# Protoboard_MX4-7-6.net
KiCad netlist of a schematic drawn in EAGLE
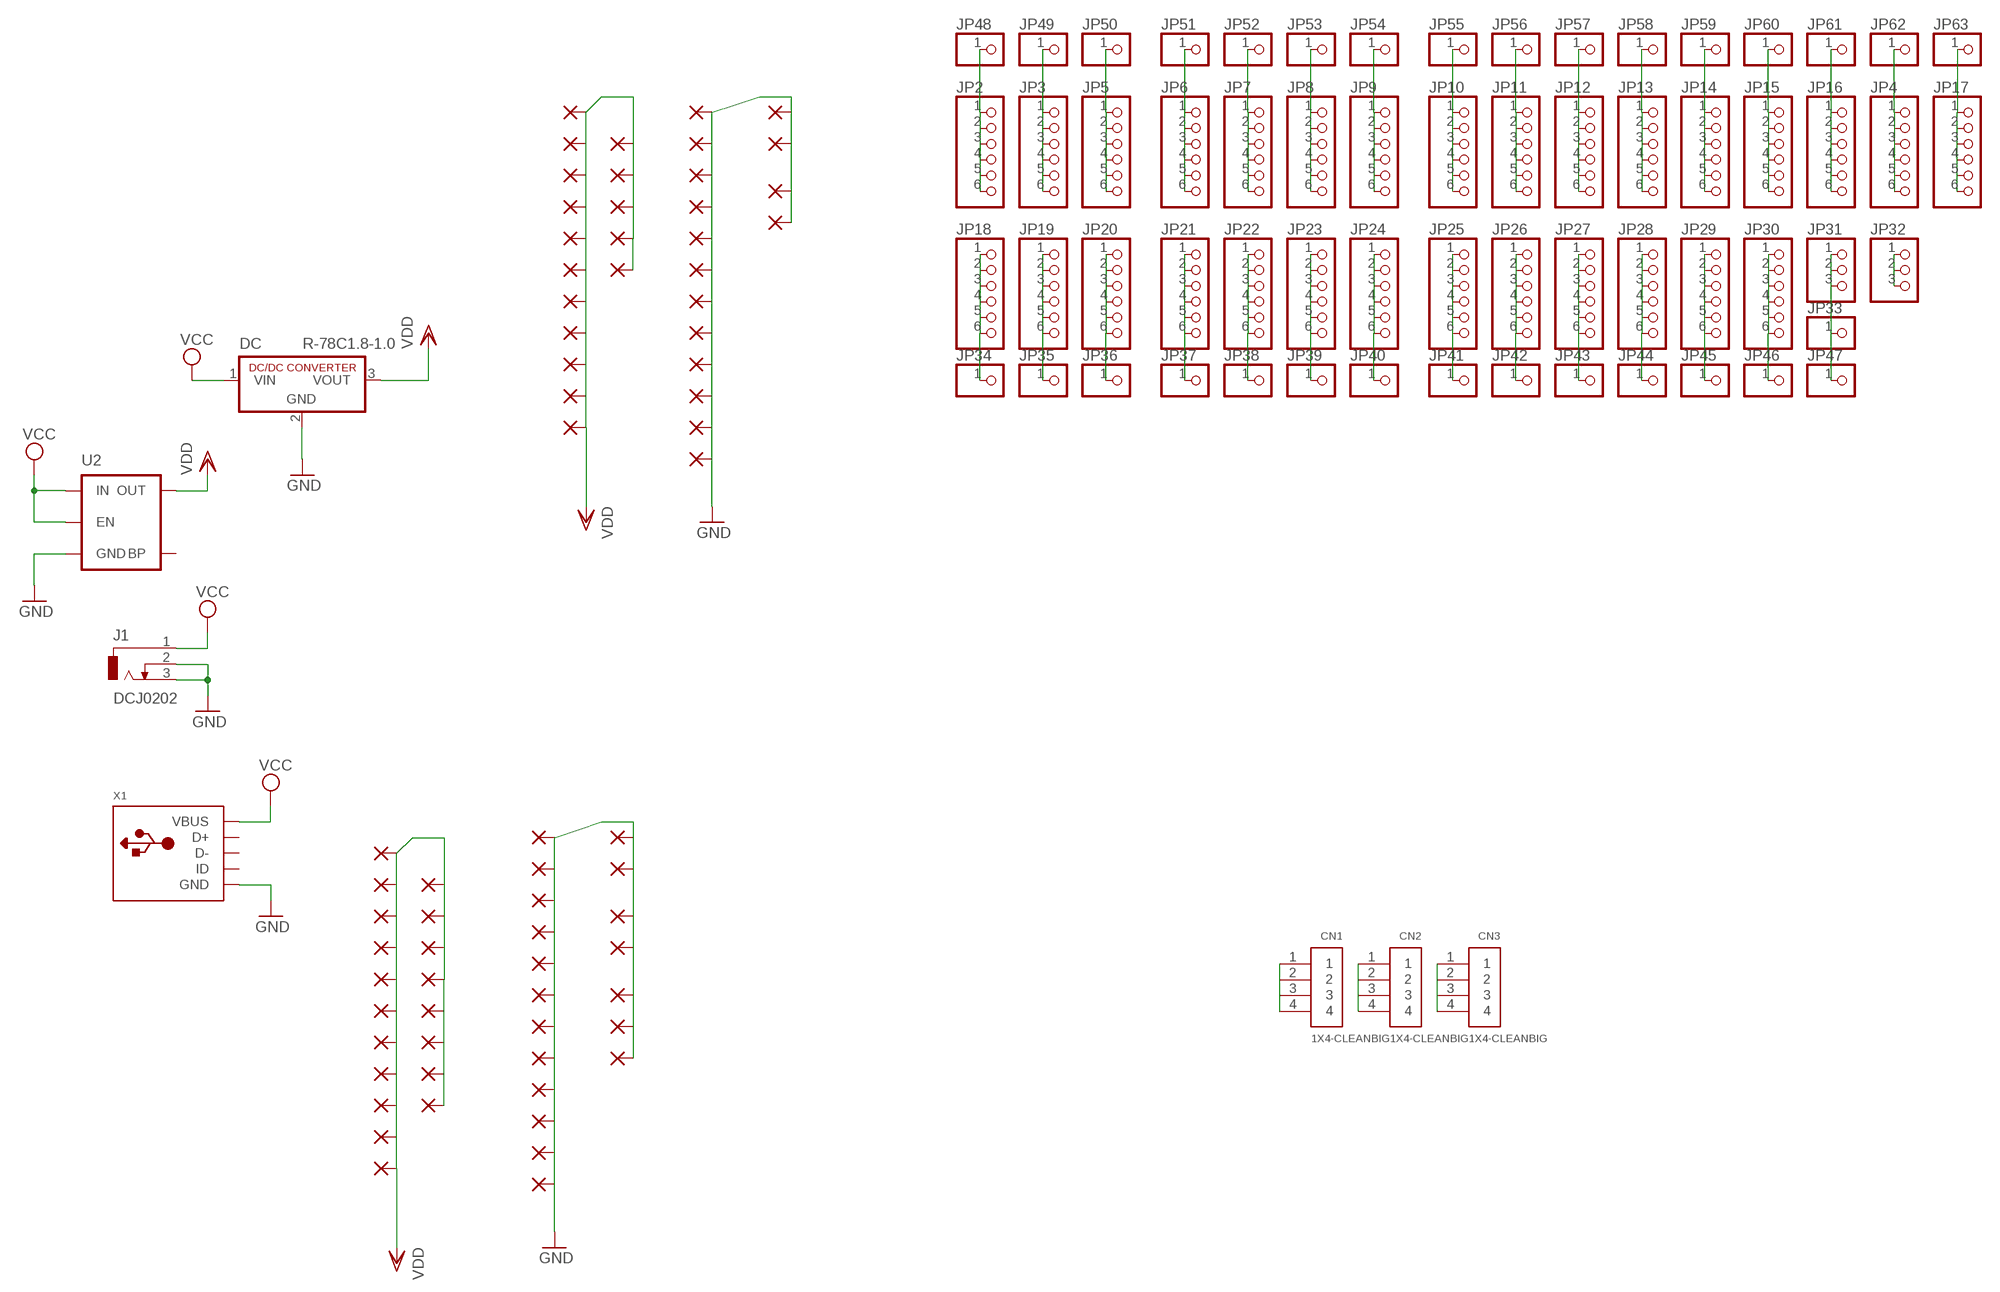
[diagram p0: schematic, sheet 1]

(export (version "E")
  (design (tool "Eeschema 10.0.6"))
  (components
    (comp (ref "CN1")
      (value "1X4-CLEANBIG")
      (footprint "eagle-import:1X04-CLEANBIG")
      (libsource (lib "eagle-import") (part "1X4-CLEANBIG"))
    )
    (comp (ref "CN2")
      (value "1X4-CLEANBIG")
      (footprint "eagle-import:1X04-CLEANBIG")
      (libsource (lib "eagle-import") (part "1X4-CLEANBIG"))
    )
    (comp (ref "CN3")
      (value "1X4-CLEANBIG")
      (footprint "eagle-import:1X04-CLEANBIG")
      (libsource (lib "eagle-import") (part "1X4-CLEANBIG"))
    )
    (comp (ref "DC")
      (value "R-78C1.8-1.0")
      (footprint "eagle-import:SIP3")
      (libsource (lib "eagle-import") (part "R-78C-1.01.8"))
    )
    (comp (ref "J1")
      (value "DCJ0202")
      (footprint "eagle-import:DCJ0202")
      (libsource (lib "eagle-import") (part "DCJ0202"))
    )
    (comp (ref "JP2")
      (value "PINHD-1X6CB")
      (footprint "eagle-import:1X06-CLEANBIG")
      (libsource (lib "eagle-import") (part "PINHD-1X6CB"))
    )
    (comp (ref "JP3")
      (value "PINHD-1X6CB")
      (footprint "eagle-import:1X06-CLEANBIG")
      (libsource (lib "eagle-import") (part "PINHD-1X6CB"))
    )
    (comp (ref "JP4")
      (value "PINHD-1X6CB")
      (footprint "eagle-import:1X06-CLEANBIG")
      (libsource (lib "eagle-import") (part "PINHD-1X6CB"))
    )
    (comp (ref "JP5")
      (value "PINHD-1X6CB")
      (footprint "eagle-import:1X06-CLEANBIG")
      (libsource (lib "eagle-import") (part "PINHD-1X6CB"))
    )
    (comp (ref "JP6")
      (value "PINHD-1X6CB")
      (footprint "eagle-import:1X06-CLEANBIG")
      (libsource (lib "eagle-import") (part "PINHD-1X6CB"))
    )
    (comp (ref "JP7")
      (value "PINHD-1X6CB")
      (footprint "eagle-import:1X06-CLEANBIG")
      (libsource (lib "eagle-import") (part "PINHD-1X6CB"))
    )
    (comp (ref "JP8")
      (value "PINHD-1X6CB")
      (footprint "eagle-import:1X06-CLEANBIG")
      (libsource (lib "eagle-import") (part "PINHD-1X6CB"))
    )
    (comp (ref "JP9")
      (value "PINHD-1X6CB")
      (footprint "eagle-import:1X06-CLEANBIG")
      (libsource (lib "eagle-import") (part "PINHD-1X6CB"))
    )
    (comp (ref "JP10")
      (value "PINHD-1X6CB")
      (footprint "eagle-import:1X06-CLEANBIG")
      (libsource (lib "eagle-import") (part "PINHD-1X6CB"))
    )
    (comp (ref "JP11")
      (value "PINHD-1X6CB")
      (footprint "eagle-import:1X06-CLEANBIG")
      (libsource (lib "eagle-import") (part "PINHD-1X6CB"))
    )
    (comp (ref "JP12")
      (value "PINHD-1X6CB")
      (footprint "eagle-import:1X06-CLEANBIG")
      (libsource (lib "eagle-import") (part "PINHD-1X6CB"))
    )
    (comp (ref "JP13")
      (value "PINHD-1X6CB")
      (footprint "eagle-import:1X06-CLEANBIG")
      (libsource (lib "eagle-import") (part "PINHD-1X6CB"))
    )
    (comp (ref "JP14")
      (value "PINHD-1X6CB")
      (footprint "eagle-import:1X06-CLEANBIG")
      (libsource (lib "eagle-import") (part "PINHD-1X6CB"))
    )
    (comp (ref "JP15")
      (value "PINHD-1X6CB")
      (footprint "eagle-import:1X06-CLEANBIG")
      (libsource (lib "eagle-import") (part "PINHD-1X6CB"))
    )
    (comp (ref "JP16")
      (value "PINHD-1X6CB")
      (footprint "eagle-import:1X06-CLEANBIG")
      (libsource (lib "eagle-import") (part "PINHD-1X6CB"))
    )
    (comp (ref "JP17")
      (value "PINHD-1X6CB")
      (footprint "eagle-import:1X06-CLEANBIG")
      (libsource (lib "eagle-import") (part "PINHD-1X6CB"))
    )
    (comp (ref "JP18")
      (value "PINHD-1X6CB")
      (footprint "eagle-import:1X06-CLEANBIG")
      (libsource (lib "eagle-import") (part "PINHD-1X6CB"))
    )
    (comp (ref "JP19")
      (value "PINHD-1X6CB")
      (footprint "eagle-import:1X06-CLEANBIG")
      (libsource (lib "eagle-import") (part "PINHD-1X6CB"))
    )
    (comp (ref "JP20")
      (value "PINHD-1X6CB")
      (footprint "eagle-import:1X06-CLEANBIG")
      (libsource (lib "eagle-import") (part "PINHD-1X6CB"))
    )
    (comp (ref "JP21")
      (value "PINHD-1X6CB")
      (footprint "eagle-import:1X06-CLEANBIG")
      (libsource (lib "eagle-import") (part "PINHD-1X6CB"))
    )
    (comp (ref "JP22")
      (value "PINHD-1X6CB")
      (footprint "eagle-import:1X06-CLEANBIG")
      (libsource (lib "eagle-import") (part "PINHD-1X6CB"))
    )
    (comp (ref "JP23")
      (value "PINHD-1X6CB")
      (footprint "eagle-import:1X06-CLEANBIG")
      (libsource (lib "eagle-import") (part "PINHD-1X6CB"))
    )
    (comp (ref "JP24")
      (value "PINHD-1X6CB")
      (footprint "eagle-import:1X06-CLEANBIG")
      (libsource (lib "eagle-import") (part "PINHD-1X6CB"))
    )
    (comp (ref "JP25")
      (value "PINHD-1X6CB")
      (footprint "eagle-import:1X06-CLEANBIG")
      (libsource (lib "eagle-import") (part "PINHD-1X6CB"))
    )
    (comp (ref "JP26")
      (value "PINHD-1X6CB")
      (footprint "eagle-import:1X06-CLEANBIG")
      (libsource (lib "eagle-import") (part "PINHD-1X6CB"))
    )
    (comp (ref "JP27")
      (value "PINHD-1X6CB")
      (footprint "eagle-import:1X06-CLEANBIG")
      (libsource (lib "eagle-import") (part "PINHD-1X6CB"))
    )
    (comp (ref "JP28")
      (value "PINHD-1X6CB")
      (footprint "eagle-import:1X06-CLEANBIG")
      (libsource (lib "eagle-import") (part "PINHD-1X6CB"))
    )
    (comp (ref "JP29")
      (value "PINHD-1X6CB")
      (footprint "eagle-import:1X06-CLEANBIG")
      (libsource (lib "eagle-import") (part "PINHD-1X6CB"))
    )
    (comp (ref "JP30")
      (value "PINHD-1X6CB")
      (footprint "eagle-import:1X06-CLEANBIG")
      (libsource (lib "eagle-import") (part "PINHD-1X6CB"))
    )
    (comp (ref "JP31")
      (value "PINHD-1X3CB")
      (footprint "eagle-import:1X03-CLEANBIG")
      (libsource (lib "eagle-import") (part "PINHD-1X3CB"))
    )
    (comp (ref "JP32")
      (value "PINHD-1X3CB")
      (footprint "eagle-import:1X03-CLEANBIG")
      (libsource (lib "eagle-import") (part "PINHD-1X3CB"))
    )
    (comp (ref "JP33")
      (value "PINHD-1X1CB")
      (footprint "eagle-import:1X01-CLEANBIG")
      (libsource (lib "eagle-import") (part "PINHD-1X1CB"))
    )
    (comp (ref "JP34")
      (value "PINHD-1X1CB")
      (footprint "eagle-import:1X01-CLEANBIG")
      (libsource (lib "eagle-import") (part "PINHD-1X1CB"))
    )
    (comp (ref "JP35")
      (value "PINHD-1X1CB")
      (footprint "eagle-import:1X01-CLEANBIG")
      (libsource (lib "eagle-import") (part "PINHD-1X1CB"))
    )
    (comp (ref "JP36")
      (value "PINHD-1X1CB")
      (footprint "eagle-import:1X01-CLEANBIG")
      (libsource (lib "eagle-import") (part "PINHD-1X1CB"))
    )
    (comp (ref "JP37")
      (value "PINHD-1X1CB")
      (footprint "eagle-import:1X01-CLEANBIG")
      (libsource (lib "eagle-import") (part "PINHD-1X1CB"))
    )
    (comp (ref "JP38")
      (value "PINHD-1X1CB")
      (footprint "eagle-import:1X01-CLEANBIG")
      (libsource (lib "eagle-import") (part "PINHD-1X1CB"))
    )
    (comp (ref "JP39")
      (value "PINHD-1X1CB")
      (footprint "eagle-import:1X01-CLEANBIG")
      (libsource (lib "eagle-import") (part "PINHD-1X1CB"))
    )
    (comp (ref "JP40")
      (value "PINHD-1X1CB")
      (footprint "eagle-import:1X01-CLEANBIG")
      (libsource (lib "eagle-import") (part "PINHD-1X1CB"))
    )
    (comp (ref "JP41")
      (value "PINHD-1X1CB")
      (footprint "eagle-import:1X01-CLEANBIG")
      (libsource (lib "eagle-import") (part "PINHD-1X1CB"))
    )
    (comp (ref "JP42")
      (value "PINHD-1X1CB")
      (footprint "eagle-import:1X01-CLEANBIG")
      (libsource (lib "eagle-import") (part "PINHD-1X1CB"))
    )
    (comp (ref "JP43")
      (value "PINHD-1X1CB")
      (footprint "eagle-import:1X01-CLEANBIG")
      (libsource (lib "eagle-import") (part "PINHD-1X1CB"))
    )
    (comp (ref "JP44")
      (value "PINHD-1X1CB")
      (footprint "eagle-import:1X01-CLEANBIG")
      (libsource (lib "eagle-import") (part "PINHD-1X1CB"))
    )
    (comp (ref "JP45")
      (value "PINHD-1X1CB")
      (footprint "eagle-import:1X01-CLEANBIG")
      (libsource (lib "eagle-import") (part "PINHD-1X1CB"))
    )
    (comp (ref "JP46")
      (value "PINHD-1X1CB")
      (footprint "eagle-import:1X01-CLEANBIG")
      (libsource (lib "eagle-import") (part "PINHD-1X1CB"))
    )
    (comp (ref "JP47")
      (value "PINHD-1X1CB")
      (footprint "eagle-import:1X01-CLEANBIG")
      (libsource (lib "eagle-import") (part "PINHD-1X1CB"))
    )
    (comp (ref "JP48")
      (value "PINHD-1X1CB")
      (footprint "eagle-import:1X01-CLEANBIG")
      (libsource (lib "eagle-import") (part "PINHD-1X1CB"))
    )
    (comp (ref "JP49")
      (value "PINHD-1X1CB")
      (footprint "eagle-import:1X01-CLEANBIG")
      (libsource (lib "eagle-import") (part "PINHD-1X1CB"))
    )
    (comp (ref "JP50")
      (value "PINHD-1X1CB")
      (footprint "eagle-import:1X01-CLEANBIG")
      (libsource (lib "eagle-import") (part "PINHD-1X1CB"))
    )
    (comp (ref "JP51")
      (value "PINHD-1X1CB")
      (footprint "eagle-import:1X01-CLEANBIG")
      (libsource (lib "eagle-import") (part "PINHD-1X1CB"))
    )
    (comp (ref "JP52")
      (value "PINHD-1X1CB")
      (footprint "eagle-import:1X01-CLEANBIG")
      (libsource (lib "eagle-import") (part "PINHD-1X1CB"))
    )
    (comp (ref "JP53")
      (value "PINHD-1X1CB")
      (footprint "eagle-import:1X01-CLEANBIG")
      (libsource (lib "eagle-import") (part "PINHD-1X1CB"))
    )
    (comp (ref "JP54")
      (value "PINHD-1X1CB")
      (footprint "eagle-import:1X01-CLEANBIG")
      (libsource (lib "eagle-import") (part "PINHD-1X1CB"))
    )
    (comp (ref "JP55")
      (value "PINHD-1X1CB")
      (footprint "eagle-import:1X01-CLEANBIG")
      (libsource (lib "eagle-import") (part "PINHD-1X1CB"))
    )
    (comp (ref "JP56")
      (value "PINHD-1X1CB")
      (footprint "eagle-import:1X01-CLEANBIG")
      (libsource (lib "eagle-import") (part "PINHD-1X1CB"))
    )
    (comp (ref "JP57")
      (value "PINHD-1X1CB")
      (footprint "eagle-import:1X01-CLEANBIG")
      (libsource (lib "eagle-import") (part "PINHD-1X1CB"))
    )
    (comp (ref "JP58")
      (value "PINHD-1X1CB")
      (footprint "eagle-import:1X01-CLEANBIG")
      (libsource (lib "eagle-import") (part "PINHD-1X1CB"))
    )
    (comp (ref "JP59")
      (value "PINHD-1X1CB")
      (footprint "eagle-import:1X01-CLEANBIG")
      (libsource (lib "eagle-import") (part "PINHD-1X1CB"))
    )
    (comp (ref "JP60")
      (value "PINHD-1X1CB")
      (footprint "eagle-import:1X01-CLEANBIG")
      (libsource (lib "eagle-import") (part "PINHD-1X1CB"))
    )
    (comp (ref "JP61")
      (value "PINHD-1X1CB")
      (footprint "eagle-import:1X01-CLEANBIG")
      (libsource (lib "eagle-import") (part "PINHD-1X1CB"))
    )
    (comp (ref "JP62")
      (value "PINHD-1X1CB")
      (footprint "eagle-import:1X01-CLEANBIG")
      (libsource (lib "eagle-import") (part "PINHD-1X1CB"))
    )
    (comp (ref "JP63")
      (value "PINHD-1X1CB")
      (footprint "eagle-import:1X01-CLEANBIG")
      (libsource (lib "eagle-import") (part "PINHD-1X1CB"))
    )
    (comp (ref "PAD4")
      (value "1,6/0,8")
      (footprint "eagle-import:1,6_0,8")
      (libsource (lib "eagle-import") (part "1,6/0,8"))
    )
    (comp (ref "PAD5")
      (value "1,6/0,8")
      (footprint "eagle-import:1,6_0,8")
      (libsource (lib "eagle-import") (part "1,6/0,8"))
    )
    (comp (ref "PAD6")
      (value "1,6/0,8")
      (footprint "eagle-import:1,6_0,8")
      (libsource (lib "eagle-import") (part "1,6/0,8"))
    )
    (comp (ref "PAD7")
      (value "1,6/0,8")
      (footprint "eagle-import:1,6_0,8")
      (libsource (lib "eagle-import") (part "1,6/0,8"))
    )
    (comp (ref "PAD8")
      (value "1,6/0,8")
      (footprint "eagle-import:1,6_0,8")
      (libsource (lib "eagle-import") (part "1,6/0,8"))
    )
    (comp (ref "PAD9")
      (value "1,6/0,8")
      (footprint "eagle-import:1,6_0,8")
      (libsource (lib "eagle-import") (part "1,6/0,8"))
    )
    (comp (ref "PAD10")
      (value "1,6/0,8")
      (footprint "eagle-import:1,6_0,8")
      (libsource (lib "eagle-import") (part "1,6/0,8"))
    )
    (comp (ref "PAD11")
      (value "1,6/0,8")
      (footprint "eagle-import:1,6_0,8")
      (libsource (lib "eagle-import") (part "1,6/0,8"))
    )
    (comp (ref "PAD12")
      (value "1,6/0,8")
      (footprint "eagle-import:1,6_0,8")
      (libsource (lib "eagle-import") (part "1,6/0,8"))
    )
    (comp (ref "PAD13")
      (value "1,6/0,8")
      (footprint "eagle-import:1,6_0,8")
      (libsource (lib "eagle-import") (part "1,6/0,8"))
    )
    (comp (ref "PAD14")
      (value "1,6/0,8")
      (footprint "eagle-import:1,6_0,8")
      (libsource (lib "eagle-import") (part "1,6/0,8"))
    )
    (comp (ref "PAD15")
      (value "1,6/0,8")
      (footprint "eagle-import:1,6_0,8")
      (libsource (lib "eagle-import") (part "1,6/0,8"))
    )
    (comp (ref "PAD16")
      (value "1,6/0,8")
      (footprint "eagle-import:1,6_0,8")
      (libsource (lib "eagle-import") (part "1,6/0,8"))
    )
    (comp (ref "PAD17")
      (value "1,6/0,8")
      (footprint "eagle-import:1,6_0,8")
      (libsource (lib "eagle-import") (part "1,6/0,8"))
    )
    (comp (ref "PAD18")
      (value "1,6/0,8")
      (footprint "eagle-import:1,6_0,8")
      (libsource (lib "eagle-import") (part "1,6/0,8"))
    )
    (comp (ref "PAD19")
      (value "1,6/0,8")
      (footprint "eagle-import:1,6_0,8")
      (libsource (lib "eagle-import") (part "1,6/0,8"))
    )
    (comp (ref "PAD20")
      (value "1,6/0,8")
      (footprint "eagle-import:1,6_0,8")
      (libsource (lib "eagle-import") (part "1,6/0,8"))
    )
    (comp (ref "PAD21")
      (value "1,6/0,8")
      (footprint "eagle-import:1,6_0,8")
      (libsource (lib "eagle-import") (part "1,6/0,8"))
    )
    (comp (ref "PAD22")
      (value "1,6/0,8")
      (footprint "eagle-import:1,6_0,8")
      (libsource (lib "eagle-import") (part "1,6/0,8"))
    )
    (comp (ref "PAD23")
      (value "1,6/0,8")
      (footprint "eagle-import:1,6_0,8")
      (libsource (lib "eagle-import") (part "1,6/0,8"))
    )
    (comp (ref "PAD24")
      (value "1,6/0,8")
      (footprint "eagle-import:1,6_0,8")
      (libsource (lib "eagle-import") (part "1,6/0,8"))
    )
    (comp (ref "PAD25")
      (value "1,6/0,8")
      (footprint "eagle-import:1,6_0,8")
      (libsource (lib "eagle-import") (part "1,6/0,8"))
    )
    (comp (ref "PAD26")
      (value "1,6/0,8")
      (footprint "eagle-import:1,6_0,8")
      (libsource (lib "eagle-import") (part "1,6/0,8"))
    )
    (comp (ref "PAD27")
      (value "1,6/0,8")
      (footprint "eagle-import:1,6_0,8")
      (libsource (lib "eagle-import") (part "1,6/0,8"))
    )
    (comp (ref "PAD28")
      (value "1,6/0,8")
      (footprint "eagle-import:1,6_0,8")
      (libsource (lib "eagle-import") (part "1,6/0,8"))
    )
    (comp (ref "PAD29")
      (value "1,6/0,8")
      (footprint "eagle-import:1,6_0,8")
      (libsource (lib "eagle-import") (part "1,6/0,8"))
    )
    (comp (ref "PAD30")
      (value "1,6/0,8")
      (footprint "eagle-import:1,6_0,8")
      (libsource (lib "eagle-import") (part "1,6/0,8"))
    )
    (comp (ref "PAD31")
      (value "1,6/0,8")
      (footprint "eagle-import:1,6_0,8")
      (libsource (lib "eagle-import") (part "1,6/0,8"))
    )
    (comp (ref "PAD32")
      (value "1,6/0,8")
      (footprint "eagle-import:1,6_0,8")
      (libsource (lib "eagle-import") (part "1,6/0,8"))
    )
    (comp (ref "PAD33")
      (value "1,6/0,8")
      (footprint "eagle-import:1,6_0,8")
      (libsource (lib "eagle-import") (part "1,6/0,8"))
    )
    (comp (ref "PAD36")
      (value "1,6/0,8")
      (footprint "eagle-import:1,6_0,8")
      (libsource (lib "eagle-import") (part "1,6/0,8"))
    )
    (comp (ref "PAD38")
      (value "1,6/0,8")
      (footprint "eagle-import:1,6_0,8")
      (libsource (lib "eagle-import") (part "1,6/0,8"))
    )
    (comp (ref "PAD421")
      (value "1,6/0,8")
      (footprint "eagle-import:1,6_0,8")
      (libsource (lib "eagle-import") (part "1,6/0,8"))
    )
    (comp (ref "PAD422")
      (value "1,6/0,8")
      (footprint "eagle-import:1,6_0,8")
      (libsource (lib "eagle-import") (part "1,6/0,8"))
    )
    (comp (ref "PAD423")
      (value "1,6/0,8")
      (footprint "eagle-import:1,6_0,8")
      (libsource (lib "eagle-import") (part "1,6/0,8"))
    )
    (comp (ref "PAD424")
      (value "1,6/0,8")
      (footprint "eagle-import:1,6_0,8")
      (libsource (lib "eagle-import") (part "1,6/0,8"))
    )
    (comp (ref "PAD425")
      (value "1,6/0,8")
      (footprint "eagle-import:1,6_0,8")
      (libsource (lib "eagle-import") (part "1,6/0,8"))
    )
    (comp (ref "PAD426")
      (value "1,6/0,8")
      (footprint "eagle-import:1,6_0,8")
      (libsource (lib "eagle-import") (part "1,6/0,8"))
    )
    (comp (ref "PAD427")
      (value "1,6/0,8")
      (footprint "eagle-import:1,6_0,8")
      (libsource (lib "eagle-import") (part "1,6/0,8"))
    )
    (comp (ref "PAD428")
      (value "1,6/0,8")
      (footprint "eagle-import:1,6_0,8")
      (libsource (lib "eagle-import") (part "1,6/0,8"))
    )
    (comp (ref "PAD429")
      (value "1,6/0,8")
      (footprint "eagle-import:1,6_0,8")
      (libsource (lib "eagle-import") (part "1,6/0,8"))
    )
    (comp (ref "PAD430")
      (value "1,6/0,8")
      (footprint "eagle-import:1,6_0,8")
      (libsource (lib "eagle-import") (part "1,6/0,8"))
    )
    (comp (ref "PAD431")
      (value "1,6/0,8")
      (footprint "eagle-import:1,6_0,8")
      (libsource (lib "eagle-import") (part "1,6/0,8"))
    )
    (comp (ref "PAD432")
      (value "1,6/0,8")
      (footprint "eagle-import:1,6_0,8")
      (libsource (lib "eagle-import") (part "1,6/0,8"))
    )
    (comp (ref "PAD433")
      (value "1,6/0,8")
      (footprint "eagle-import:1,6_0,8")
      (libsource (lib "eagle-import") (part "1,6/0,8"))
    )
    (comp (ref "PAD434")
      (value "1,6/0,8")
      (footprint "eagle-import:1,6_0,8")
      (libsource (lib "eagle-import") (part "1,6/0,8"))
    )
    (comp (ref "PAD435")
      (value "1,6/0,8")
      (footprint "eagle-import:1,6_0,8")
      (libsource (lib "eagle-import") (part "1,6/0,8"))
    )
    (comp (ref "PAD436")
      (value "1,6/0,8")
      (footprint "eagle-import:1,6_0,8")
      (libsource (lib "eagle-import") (part "1,6/0,8"))
    )
    (comp (ref "PAD439")
      (value "1,6/0,8")
      (footprint "eagle-import:1,6_0,8")
      (libsource (lib "eagle-import") (part "1,6/0,8"))
    )
    (comp (ref "PAD440")
      (value "1,6/0,8")
      (footprint "eagle-import:1,6_0,8")
      (libsource (lib "eagle-import") (part "1,6/0,8"))
    )
    (comp (ref "PAD441")
      (value "1,6/0,8")
      (footprint "eagle-import:1,6_0,8")
      (libsource (lib "eagle-import") (part "1,6/0,8"))
    )
    (comp (ref "PAD442")
      (value "1,6/0,8")
      (footprint "eagle-import:1,6_0,8")
      (libsource (lib "eagle-import") (part "1,6/0,8"))
    )
    (comp (ref "PAD443")
      (value "1,6/0,8")
      (footprint "eagle-import:1,6_0,8")
      (libsource (lib "eagle-import") (part "1,6/0,8"))
    )
    (comp (ref "PAD444")
      (value "1,6/0,8")
      (footprint "eagle-import:1,6_0,8")
      (libsource (lib "eagle-import") (part "1,6/0,8"))
    )
    (comp (ref "PAD445")
      (value "1,6/0,8")
      (footprint "eagle-import:1,6_0,8")
      (libsource (lib "eagle-import") (part "1,6/0,8"))
    )
    (comp (ref "PAD446")
      (value "1,6/0,8")
      (footprint "eagle-import:1,6_0,8")
      (libsource (lib "eagle-import") (part "1,6/0,8"))
    )
    (comp (ref "PAD447")
      (value "1,6/0,8")
      (footprint "eagle-import:1,6_0,8")
      (libsource (lib "eagle-import") (part "1,6/0,8"))
    )
    (comp (ref "PAD448")
      (value "1,6/0,8")
      (footprint "eagle-import:1,6_0,8")
      (libsource (lib "eagle-import") (part "1,6/0,8"))
    )
    (comp (ref "PAD449")
      (value "1,6/0,8")
      (footprint "eagle-import:1,6_0,8")
      (libsource (lib "eagle-import") (part "1,6/0,8"))
    )
    (comp (ref "PAD450")
      (value "1,6/0,8")
      (footprint "eagle-import:1,6_0,8")
      (libsource (lib "eagle-import") (part "1,6/0,8"))
    )
    (comp (ref "PAD451")
      (value "1,6/0,8")
      (footprint "eagle-import:1,6_0,8")
      (libsource (lib "eagle-import") (part "1,6/0,8"))
    )
    (comp (ref "PAD452")
      (value "1,6/0,8")
      (footprint "eagle-import:1,6_0,8")
      (libsource (lib "eagle-import") (part "1,6/0,8"))
    )
    (comp (ref "PAD453")
      (value "1,6/0,8")
      (footprint "eagle-import:1,6_0,8")
      (libsource (lib "eagle-import") (part "1,6/0,8"))
    )
    (comp (ref "PAD454")
      (value "1,6/0,8")
      (footprint "eagle-import:1,6_0,8")
      (libsource (lib "eagle-import") (part "1,6/0,8"))
    )
    (comp (ref "PAD455")
      (value "1,6/0,8")
      (footprint "eagle-import:1,6_0,8")
      (libsource (lib "eagle-import") (part "1,6/0,8"))
    )
    (comp (ref "PAD456")
      (value "1,6/0,8")
      (footprint "eagle-import:1,6_0,8")
      (libsource (lib "eagle-import") (part "1,6/0,8"))
    )
    (comp (ref "PAD459")
      (value "1,6/0,8")
      (footprint "eagle-import:1,6_0,8")
      (libsource (lib "eagle-import") (part "1,6/0,8"))
    )
    (comp (ref "PAD460")
      (value "1,6/0,8")
      (footprint "eagle-import:1,6_0,8")
      (libsource (lib "eagle-import") (part "1,6/0,8"))
    )
    (comp (ref "PAD461")
      (value "1,6/0,8")
      (footprint "eagle-import:1,6_0,8")
      (libsource (lib "eagle-import") (part "1,6/0,8"))
    )
    (comp (ref "PAD462")
      (value "1,6/0,8")
      (footprint "eagle-import:1,6_0,8")
      (libsource (lib "eagle-import") (part "1,6/0,8"))
    )
    (comp (ref "U2")
      (value "MIC52053.3V")
      (footprint "eagle-import:SOT23-5")
      (libsource (lib "eagle-import") (part "MIC52053.3V"))
    )
    (comp (ref "X1")
      (value "USBMICRO_20329")
      (footprint "eagle-import:4UCONN_20329")
      (libsource (lib "eagle-import") (part "USBMICRO_20329"))
    )
  )
  (nets
    (net (code "1") (name "GND") (class "Default")
      (node (ref "DC") (pin "2") (pinfunction "GND_2") (pintype "passive"))
      (node (ref "J1") (pin "2") (pinfunction "2_2") (pintype "passive"))
      (node (ref "J1") (pin "3") (pinfunction "3_3") (pintype "passive"))
      (node (ref "PAD17") (pin "1") (pinfunction "P_1") (pintype "passive"))
      (node (ref "PAD22") (pin "1") (pinfunction "P_1") (pintype "passive"))
      (node (ref "PAD23") (pin "1") (pinfunction "P_1") (pintype "passive"))
      (node (ref "PAD24") (pin "1") (pinfunction "P_1") (pintype "passive"))
      (node (ref "PAD25") (pin "1") (pinfunction "P_1") (pintype "passive"))
      (node (ref "PAD26") (pin "1") (pinfunction "P_1") (pintype "passive"))
      (node (ref "PAD27") (pin "1") (pinfunction "P_1") (pintype "passive"))
      (node (ref "PAD28") (pin "1") (pinfunction "P_1") (pintype "passive"))
      (node (ref "PAD29") (pin "1") (pinfunction "P_1") (pintype "passive"))
      (node (ref "PAD30") (pin "1") (pinfunction "P_1") (pintype "passive"))
      (node (ref "PAD31") (pin "1") (pinfunction "P_1") (pintype "passive"))
      (node (ref "PAD32") (pin "1") (pinfunction "P_1") (pintype "passive"))
      (node (ref "PAD33") (pin "1") (pinfunction "P_1") (pintype "passive"))
      (node (ref "PAD36") (pin "1") (pinfunction "P_1") (pintype "passive"))
      (node (ref "PAD38") (pin "1") (pinfunction "P_1") (pintype "passive"))
      (node (ref "PAD4") (pin "1") (pinfunction "P_1") (pintype "passive"))
      (node (ref "PAD421") (pin "1") (pinfunction "P_1") (pintype "passive"))
      (node (ref "PAD422") (pin "1") (pinfunction "P_1") (pintype "passive"))
      (node (ref "PAD423") (pin "1") (pinfunction "P_1") (pintype "passive"))
      (node (ref "PAD424") (pin "1") (pinfunction "P_1") (pintype "passive"))
      (node (ref "PAD425") (pin "1") (pinfunction "P_1") (pintype "passive"))
      (node (ref "PAD426") (pin "1") (pinfunction "P_1") (pintype "passive"))
      (node (ref "PAD427") (pin "1") (pinfunction "P_1") (pintype "passive"))
      (node (ref "PAD428") (pin "1") (pinfunction "P_1") (pintype "passive"))
      (node (ref "PAD429") (pin "1") (pinfunction "P_1") (pintype "passive"))
      (node (ref "PAD430") (pin "1") (pinfunction "P_1") (pintype "passive"))
      (node (ref "PAD431") (pin "1") (pinfunction "P_1") (pintype "passive"))
      (node (ref "PAD432") (pin "1") (pinfunction "P_1") (pintype "passive"))
      (node (ref "PAD433") (pin "1") (pinfunction "P_1") (pintype "passive"))
      (node (ref "PAD434") (pin "1") (pinfunction "P_1") (pintype "passive"))
      (node (ref "PAD435") (pin "1") (pinfunction "P_1") (pintype "passive"))
      (node (ref "PAD436") (pin "1") (pinfunction "P_1") (pintype "passive"))
      (node (ref "PAD439") (pin "1") (pinfunction "P_1") (pintype "passive"))
      (node (ref "PAD440") (pin "1") (pinfunction "P_1") (pintype "passive"))
      (node (ref "PAD441") (pin "1") (pinfunction "P_1") (pintype "passive"))
      (node (ref "U2") (pin "2") (pinfunction "GND_2") (pintype "input"))
      (node (ref "X1") (pin "BASE@1") (pinfunction "GND_BASE@1") (pintype "power_in"))
      (node (ref "X1") (pin "BASE@2") (pinfunction "GND_BASE@2") (pintype "power_in"))
      (node (ref "X1") (pin "GND") (pinfunction "GND_GND") (pintype "power_in"))
      (node (ref "X1") (pin "SPRT@1") (pinfunction "GND_SPRT@1") (pintype "power_in"))
      (node (ref "X1") (pin "SPRT@2") (pinfunction "GND_SPRT@2") (pintype "power_in"))
      (node (ref "X1") (pin "SPRT@3") (pinfunction "GND_SPRT@3") (pintype "power_in"))
      (node (ref "X1") (pin "SPRT@4") (pinfunction "GND_SPRT@4") (pintype "power_in"))
    )
    (net (code "2") (name "Net-(CN1-Pad1)") (class "Default")
      (node (ref "CN1") (pin "1") (pinfunction "1_1") (pintype "bidirectional"))
      (node (ref "CN1") (pin "2") (pinfunction "2_2") (pintype "bidirectional"))
      (node (ref "CN1") (pin "3") (pinfunction "3_3") (pintype "bidirectional"))
      (node (ref "CN1") (pin "4") (pinfunction "4_4") (pintype "bidirectional"))
    )
    (net (code "3") (name "Net-(CN2-Pad1)") (class "Default")
      (node (ref "CN2") (pin "1") (pinfunction "1_1") (pintype "bidirectional"))
      (node (ref "CN2") (pin "2") (pinfunction "2_2") (pintype "bidirectional"))
      (node (ref "CN2") (pin "3") (pinfunction "3_3") (pintype "bidirectional"))
      (node (ref "CN2") (pin "4") (pinfunction "4_4") (pintype "bidirectional"))
    )
    (net (code "4") (name "Net-(CN3-Pad1)") (class "Default")
      (node (ref "CN3") (pin "1") (pinfunction "1_1") (pintype "bidirectional"))
      (node (ref "CN3") (pin "2") (pinfunction "2_2") (pintype "bidirectional"))
      (node (ref "CN3") (pin "3") (pinfunction "3_3") (pintype "bidirectional"))
      (node (ref "CN3") (pin "4") (pinfunction "4_4") (pintype "bidirectional"))
    )
    (net (code "5") (name "Net-(JP2-Pad1)") (class "Default")
      (node (ref "JP2") (pin "1") (pinfunction "1_1") (pintype "passive"))
      (node (ref "JP2") (pin "2") (pinfunction "2_2") (pintype "passive"))
      (node (ref "JP2") (pin "3") (pinfunction "3_3") (pintype "passive"))
      (node (ref "JP2") (pin "4") (pinfunction "4_4") (pintype "passive"))
      (node (ref "JP2") (pin "5") (pinfunction "5_5") (pintype "passive"))
      (node (ref "JP2") (pin "6") (pinfunction "6_6") (pintype "passive"))
      (node (ref "JP48") (pin "1") (pinfunction "1_1") (pintype "passive"))
    )
    (net (code "6") (name "Net-(JP3-Pad1)") (class "Default")
      (node (ref "JP3") (pin "1") (pinfunction "1_1") (pintype "passive"))
      (node (ref "JP3") (pin "2") (pinfunction "2_2") (pintype "passive"))
      (node (ref "JP3") (pin "3") (pinfunction "3_3") (pintype "passive"))
      (node (ref "JP3") (pin "4") (pinfunction "4_4") (pintype "passive"))
      (node (ref "JP3") (pin "5") (pinfunction "5_5") (pintype "passive"))
      (node (ref "JP3") (pin "6") (pinfunction "6_6") (pintype "passive"))
      (node (ref "JP49") (pin "1") (pinfunction "1_1") (pintype "passive"))
    )
    (net (code "7") (name "Net-(JP4-Pad1)") (class "Default")
      (node (ref "JP4") (pin "1") (pinfunction "1_1") (pintype "passive"))
      (node (ref "JP4") (pin "2") (pinfunction "2_2") (pintype "passive"))
      (node (ref "JP4") (pin "3") (pinfunction "3_3") (pintype "passive"))
      (node (ref "JP4") (pin "4") (pinfunction "4_4") (pintype "passive"))
      (node (ref "JP4") (pin "5") (pinfunction "5_5") (pintype "passive"))
      (node (ref "JP4") (pin "6") (pinfunction "6_6") (pintype "passive"))
      (node (ref "JP62") (pin "1") (pinfunction "1_1") (pintype "passive"))
    )
    (net (code "8") (name "Net-(JP5-Pad1)") (class "Default")
      (node (ref "JP5") (pin "1") (pinfunction "1_1") (pintype "passive"))
      (node (ref "JP5") (pin "2") (pinfunction "2_2") (pintype "passive"))
      (node (ref "JP5") (pin "3") (pinfunction "3_3") (pintype "passive"))
      (node (ref "JP5") (pin "4") (pinfunction "4_4") (pintype "passive"))
      (node (ref "JP5") (pin "5") (pinfunction "5_5") (pintype "passive"))
      (node (ref "JP5") (pin "6") (pinfunction "6_6") (pintype "passive"))
      (node (ref "JP50") (pin "1") (pinfunction "1_1") (pintype "passive"))
    )
    (net (code "9") (name "Net-(JP10-Pad1)") (class "Default")
      (node (ref "JP10") (pin "1") (pinfunction "1_1") (pintype "passive"))
      (node (ref "JP10") (pin "2") (pinfunction "2_2") (pintype "passive"))
      (node (ref "JP10") (pin "3") (pinfunction "3_3") (pintype "passive"))
      (node (ref "JP10") (pin "4") (pinfunction "4_4") (pintype "passive"))
      (node (ref "JP10") (pin "5") (pinfunction "5_5") (pintype "passive"))
      (node (ref "JP10") (pin "6") (pinfunction "6_6") (pintype "passive"))
      (node (ref "JP55") (pin "1") (pinfunction "1_1") (pintype "passive"))
    )
    (net (code "10") (name "Net-(JP11-Pad1)") (class "Default")
      (node (ref "JP11") (pin "1") (pinfunction "1_1") (pintype "passive"))
      (node (ref "JP11") (pin "2") (pinfunction "2_2") (pintype "passive"))
      (node (ref "JP11") (pin "3") (pinfunction "3_3") (pintype "passive"))
      (node (ref "JP11") (pin "4") (pinfunction "4_4") (pintype "passive"))
      (node (ref "JP11") (pin "5") (pinfunction "5_5") (pintype "passive"))
      (node (ref "JP11") (pin "6") (pinfunction "6_6") (pintype "passive"))
      (node (ref "JP56") (pin "1") (pinfunction "1_1") (pintype "passive"))
    )
    (net (code "11") (name "Net-(JP12-Pad1)") (class "Default")
      (node (ref "JP12") (pin "1") (pinfunction "1_1") (pintype "passive"))
      (node (ref "JP12") (pin "2") (pinfunction "2_2") (pintype "passive"))
      (node (ref "JP12") (pin "3") (pinfunction "3_3") (pintype "passive"))
      (node (ref "JP12") (pin "4") (pinfunction "4_4") (pintype "passive"))
      (node (ref "JP12") (pin "5") (pinfunction "5_5") (pintype "passive"))
      (node (ref "JP12") (pin "6") (pinfunction "6_6") (pintype "passive"))
      (node (ref "JP57") (pin "1") (pinfunction "1_1") (pintype "passive"))
    )
    (net (code "12") (name "Net-(JP13-Pad1)") (class "Default")
      (node (ref "JP13") (pin "1") (pinfunction "1_1") (pintype "passive"))
      (node (ref "JP13") (pin "2") (pinfunction "2_2") (pintype "passive"))
      (node (ref "JP13") (pin "3") (pinfunction "3_3") (pintype "passive"))
      (node (ref "JP13") (pin "4") (pinfunction "4_4") (pintype "passive"))
      (node (ref "JP13") (pin "5") (pinfunction "5_5") (pintype "passive"))
      (node (ref "JP13") (pin "6") (pinfunction "6_6") (pintype "passive"))
      (node (ref "JP58") (pin "1") (pinfunction "1_1") (pintype "passive"))
    )
    (net (code "13") (name "Net-(JP14-Pad1)") (class "Default")
      (node (ref "JP14") (pin "1") (pinfunction "1_1") (pintype "passive"))
      (node (ref "JP14") (pin "2") (pinfunction "2_2") (pintype "passive"))
      (node (ref "JP14") (pin "3") (pinfunction "3_3") (pintype "passive"))
      (node (ref "JP14") (pin "4") (pinfunction "4_4") (pintype "passive"))
      (node (ref "JP14") (pin "5") (pinfunction "5_5") (pintype "passive"))
      (node (ref "JP14") (pin "6") (pinfunction "6_6") (pintype "passive"))
      (node (ref "JP59") (pin "1") (pinfunction "1_1") (pintype "passive"))
    )
    (net (code "14") (name "Net-(JP15-Pad1)") (class "Default")
      (node (ref "JP15") (pin "1") (pinfunction "1_1") (pintype "passive"))
      (node (ref "JP15") (pin "2") (pinfunction "2_2") (pintype "passive"))
      (node (ref "JP15") (pin "3") (pinfunction "3_3") (pintype "passive"))
      (node (ref "JP15") (pin "4") (pinfunction "4_4") (pintype "passive"))
      (node (ref "JP15") (pin "5") (pinfunction "5_5") (pintype "passive"))
      (node (ref "JP15") (pin "6") (pinfunction "6_6") (pintype "passive"))
      (node (ref "JP60") (pin "1") (pinfunction "1_1") (pintype "passive"))
    )
    (net (code "15") (name "Net-(JP16-Pad1)") (class "Default")
      (node (ref "JP16") (pin "1") (pinfunction "1_1") (pintype "passive"))
      (node (ref "JP16") (pin "2") (pinfunction "2_2") (pintype "passive"))
      (node (ref "JP16") (pin "3") (pinfunction "3_3") (pintype "passive"))
      (node (ref "JP16") (pin "4") (pinfunction "4_4") (pintype "passive"))
      (node (ref "JP16") (pin "5") (pinfunction "5_5") (pintype "passive"))
      (node (ref "JP16") (pin "6") (pinfunction "6_6") (pintype "passive"))
      (node (ref "JP61") (pin "1") (pinfunction "1_1") (pintype "passive"))
    )
    (net (code "16") (name "Net-(JP17-Pad1)") (class "Default")
      (node (ref "JP17") (pin "1") (pinfunction "1_1") (pintype "passive"))
      (node (ref "JP17") (pin "2") (pinfunction "2_2") (pintype "passive"))
      (node (ref "JP17") (pin "3") (pinfunction "3_3") (pintype "passive"))
      (node (ref "JP17") (pin "4") (pinfunction "4_4") (pintype "passive"))
      (node (ref "JP17") (pin "5") (pinfunction "5_5") (pintype "passive"))
      (node (ref "JP17") (pin "6") (pinfunction "6_6") (pintype "passive"))
      (node (ref "JP63") (pin "1") (pinfunction "1_1") (pintype "passive"))
    )
    (net (code "17") (name "Net-(JP18-Pad1)") (class "Default")
      (node (ref "JP18") (pin "1") (pinfunction "1_1") (pintype "passive"))
      (node (ref "JP18") (pin "2") (pinfunction "2_2") (pintype "passive"))
      (node (ref "JP18") (pin "3") (pinfunction "3_3") (pintype "passive"))
      (node (ref "JP18") (pin "4") (pinfunction "4_4") (pintype "passive"))
      (node (ref "JP18") (pin "5") (pinfunction "5_5") (pintype "passive"))
      (node (ref "JP18") (pin "6") (pinfunction "6_6") (pintype "passive"))
      (node (ref "JP34") (pin "1") (pinfunction "1_1") (pintype "passive"))
    )
    (net (code "18") (name "Net-(JP19-Pad1)") (class "Default")
      (node (ref "JP19") (pin "1") (pinfunction "1_1") (pintype "passive"))
      (node (ref "JP19") (pin "2") (pinfunction "2_2") (pintype "passive"))
      (node (ref "JP19") (pin "3") (pinfunction "3_3") (pintype "passive"))
      (node (ref "JP19") (pin "4") (pinfunction "4_4") (pintype "passive"))
      (node (ref "JP19") (pin "5") (pinfunction "5_5") (pintype "passive"))
      (node (ref "JP19") (pin "6") (pinfunction "6_6") (pintype "passive"))
      (node (ref "JP35") (pin "1") (pinfunction "1_1") (pintype "passive"))
    )
    (net (code "19") (name "Net-(JP20-Pad1)") (class "Default")
      (node (ref "JP20") (pin "1") (pinfunction "1_1") (pintype "passive"))
      (node (ref "JP20") (pin "2") (pinfunction "2_2") (pintype "passive"))
      (node (ref "JP20") (pin "3") (pinfunction "3_3") (pintype "passive"))
      (node (ref "JP20") (pin "4") (pinfunction "4_4") (pintype "passive"))
      (node (ref "JP20") (pin "5") (pinfunction "5_5") (pintype "passive"))
      (node (ref "JP20") (pin "6") (pinfunction "6_6") (pintype "passive"))
      (node (ref "JP36") (pin "1") (pinfunction "1_1") (pintype "passive"))
    )
    (net (code "20") (name "Net-(JP21-Pad1)") (class "Default")
      (node (ref "JP21") (pin "1") (pinfunction "1_1") (pintype "passive"))
      (node (ref "JP21") (pin "2") (pinfunction "2_2") (pintype "passive"))
      (node (ref "JP21") (pin "3") (pinfunction "3_3") (pintype "passive"))
      (node (ref "JP21") (pin "4") (pinfunction "4_4") (pintype "passive"))
      (node (ref "JP21") (pin "5") (pinfunction "5_5") (pintype "passive"))
      (node (ref "JP21") (pin "6") (pinfunction "6_6") (pintype "passive"))
      (node (ref "JP37") (pin "1") (pinfunction "1_1") (pintype "passive"))
    )
    (net (code "21") (name "Net-(JP22-Pad1)") (class "Default")
      (node (ref "JP22") (pin "1") (pinfunction "1_1") (pintype "passive"))
      (node (ref "JP22") (pin "2") (pinfunction "2_2") (pintype "passive"))
      (node (ref "JP22") (pin "3") (pinfunction "3_3") (pintype "passive"))
      (node (ref "JP22") (pin "4") (pinfunction "4_4") (pintype "passive"))
      (node (ref "JP22") (pin "5") (pinfunction "5_5") (pintype "passive"))
      (node (ref "JP22") (pin "6") (pinfunction "6_6") (pintype "passive"))
      (node (ref "JP38") (pin "1") (pinfunction "1_1") (pintype "passive"))
    )
    (net (code "22") (name "Net-(JP23-Pad1)") (class "Default")
      (node (ref "JP23") (pin "1") (pinfunction "1_1") (pintype "passive"))
      (node (ref "JP23") (pin "2") (pinfunction "2_2") (pintype "passive"))
      (node (ref "JP23") (pin "3") (pinfunction "3_3") (pintype "passive"))
      (node (ref "JP23") (pin "4") (pinfunction "4_4") (pintype "passive"))
      (node (ref "JP23") (pin "5") (pinfunction "5_5") (pintype "passive"))
      (node (ref "JP23") (pin "6") (pinfunction "6_6") (pintype "passive"))
      (node (ref "JP39") (pin "1") (pinfunction "1_1") (pintype "passive"))
    )
    (net (code "23") (name "Net-(JP24-Pad1)") (class "Default")
      (node (ref "JP24") (pin "1") (pinfunction "1_1") (pintype "passive"))
      (node (ref "JP24") (pin "2") (pinfunction "2_2") (pintype "passive"))
      (node (ref "JP24") (pin "3") (pinfunction "3_3") (pintype "passive"))
      (node (ref "JP24") (pin "4") (pinfunction "4_4") (pintype "passive"))
      (node (ref "JP24") (pin "5") (pinfunction "5_5") (pintype "passive"))
      (node (ref "JP24") (pin "6") (pinfunction "6_6") (pintype "passive"))
      (node (ref "JP40") (pin "1") (pinfunction "1_1") (pintype "passive"))
    )
    (net (code "24") (name "Net-(JP25-Pad1)") (class "Default")
      (node (ref "JP25") (pin "1") (pinfunction "1_1") (pintype "passive"))
      (node (ref "JP25") (pin "2") (pinfunction "2_2") (pintype "passive"))
      (node (ref "JP25") (pin "3") (pinfunction "3_3") (pintype "passive"))
      (node (ref "JP25") (pin "4") (pinfunction "4_4") (pintype "passive"))
      (node (ref "JP25") (pin "5") (pinfunction "5_5") (pintype "passive"))
      (node (ref "JP25") (pin "6") (pinfunction "6_6") (pintype "passive"))
      (node (ref "JP41") (pin "1") (pinfunction "1_1") (pintype "passive"))
    )
    (net (code "25") (name "Net-(JP26-Pad1)") (class "Default")
      (node (ref "JP26") (pin "1") (pinfunction "1_1") (pintype "passive"))
      (node (ref "JP26") (pin "2") (pinfunction "2_2") (pintype "passive"))
      (node (ref "JP26") (pin "3") (pinfunction "3_3") (pintype "passive"))
      (node (ref "JP26") (pin "4") (pinfunction "4_4") (pintype "passive"))
      (node (ref "JP26") (pin "5") (pinfunction "5_5") (pintype "passive"))
      (node (ref "JP26") (pin "6") (pinfunction "6_6") (pintype "passive"))
      (node (ref "JP42") (pin "1") (pinfunction "1_1") (pintype "passive"))
    )
    (net (code "26") (name "Net-(JP27-Pad1)") (class "Default")
      (node (ref "JP27") (pin "1") (pinfunction "1_1") (pintype "passive"))
      (node (ref "JP27") (pin "2") (pinfunction "2_2") (pintype "passive"))
      (node (ref "JP27") (pin "3") (pinfunction "3_3") (pintype "passive"))
      (node (ref "JP27") (pin "4") (pinfunction "4_4") (pintype "passive"))
      (node (ref "JP27") (pin "5") (pinfunction "5_5") (pintype "passive"))
      (node (ref "JP27") (pin "6") (pinfunction "6_6") (pintype "passive"))
      (node (ref "JP43") (pin "1") (pinfunction "1_1") (pintype "passive"))
    )
    (net (code "27") (name "Net-(JP28-Pad1)") (class "Default")
      (node (ref "JP28") (pin "1") (pinfunction "1_1") (pintype "passive"))
      (node (ref "JP28") (pin "2") (pinfunction "2_2") (pintype "passive"))
      (node (ref "JP28") (pin "3") (pinfunction "3_3") (pintype "passive"))
      (node (ref "JP28") (pin "4") (pinfunction "4_4") (pintype "passive"))
      (node (ref "JP28") (pin "5") (pinfunction "5_5") (pintype "passive"))
      (node (ref "JP28") (pin "6") (pinfunction "6_6") (pintype "passive"))
      (node (ref "JP44") (pin "1") (pinfunction "1_1") (pintype "passive"))
    )
    (net (code "28") (name "Net-(JP29-Pad1)") (class "Default")
      (node (ref "JP29") (pin "1") (pinfunction "1_1") (pintype "passive"))
      (node (ref "JP29") (pin "2") (pinfunction "2_2") (pintype "passive"))
      (node (ref "JP29") (pin "3") (pinfunction "3_3") (pintype "passive"))
      (node (ref "JP29") (pin "4") (pinfunction "4_4") (pintype "passive"))
      (node (ref "JP29") (pin "5") (pinfunction "5_5") (pintype "passive"))
      (node (ref "JP29") (pin "6") (pinfunction "6_6") (pintype "passive"))
      (node (ref "JP45") (pin "1") (pinfunction "1_1") (pintype "passive"))
    )
    (net (code "29") (name "Net-(JP30-Pad1)") (class "Default")
      (node (ref "JP30") (pin "1") (pinfunction "1_1") (pintype "passive"))
      (node (ref "JP30") (pin "2") (pinfunction "2_2") (pintype "passive"))
      (node (ref "JP30") (pin "3") (pinfunction "3_3") (pintype "passive"))
      (node (ref "JP30") (pin "4") (pinfunction "4_4") (pintype "passive"))
      (node (ref "JP30") (pin "5") (pinfunction "5_5") (pintype "passive"))
      (node (ref "JP30") (pin "6") (pinfunction "6_6") (pintype "passive"))
      (node (ref "JP46") (pin "1") (pinfunction "1_1") (pintype "passive"))
    )
    (net (code "30") (name "Net-(JP31-Pad1)") (class "Default")
      (node (ref "JP31") (pin "1") (pinfunction "1_1") (pintype "passive"))
      (node (ref "JP31") (pin "2") (pinfunction "2_2") (pintype "passive"))
      (node (ref "JP31") (pin "3") (pinfunction "3_3") (pintype "passive"))
      (node (ref "JP33") (pin "1") (pinfunction "1_1") (pintype "passive"))
      (node (ref "JP47") (pin "1") (pinfunction "1_1") (pintype "passive"))
    )
    (net (code "31") (name "Net-(JP32-Pad1)") (class "Default")
      (node (ref "JP32") (pin "1") (pinfunction "1_1") (pintype "passive"))
      (node (ref "JP32") (pin "2") (pinfunction "2_2") (pintype "passive"))
      (node (ref "JP32") (pin "3") (pinfunction "3_3") (pintype "passive"))
    )
    (net (code "32") (name "Net-(JP51-Pad1)") (class "Default")
      (node (ref "JP51") (pin "1") (pinfunction "1_1") (pintype "passive"))
      (node (ref "JP6") (pin "1") (pinfunction "1_1") (pintype "passive"))
      (node (ref "JP6") (pin "2") (pinfunction "2_2") (pintype "passive"))
      (node (ref "JP6") (pin "3") (pinfunction "3_3") (pintype "passive"))
      (node (ref "JP6") (pin "4") (pinfunction "4_4") (pintype "passive"))
      (node (ref "JP6") (pin "5") (pinfunction "5_5") (pintype "passive"))
      (node (ref "JP6") (pin "6") (pinfunction "6_6") (pintype "passive"))
    )
    (net (code "33") (name "Net-(JP52-Pad1)") (class "Default")
      (node (ref "JP52") (pin "1") (pinfunction "1_1") (pintype "passive"))
      (node (ref "JP7") (pin "1") (pinfunction "1_1") (pintype "passive"))
      (node (ref "JP7") (pin "2") (pinfunction "2_2") (pintype "passive"))
      (node (ref "JP7") (pin "3") (pinfunction "3_3") (pintype "passive"))
      (node (ref "JP7") (pin "4") (pinfunction "4_4") (pintype "passive"))
      (node (ref "JP7") (pin "5") (pinfunction "5_5") (pintype "passive"))
      (node (ref "JP7") (pin "6") (pinfunction "6_6") (pintype "passive"))
    )
    (net (code "34") (name "Net-(JP53-Pad1)") (class "Default")
      (node (ref "JP53") (pin "1") (pinfunction "1_1") (pintype "passive"))
      (node (ref "JP8") (pin "1") (pinfunction "1_1") (pintype "passive"))
      (node (ref "JP8") (pin "2") (pinfunction "2_2") (pintype "passive"))
      (node (ref "JP8") (pin "3") (pinfunction "3_3") (pintype "passive"))
      (node (ref "JP8") (pin "4") (pinfunction "4_4") (pintype "passive"))
      (node (ref "JP8") (pin "5") (pinfunction "5_5") (pintype "passive"))
      (node (ref "JP8") (pin "6") (pinfunction "6_6") (pintype "passive"))
    )
    (net (code "35") (name "Net-(JP54-Pad1)") (class "Default")
      (node (ref "JP54") (pin "1") (pinfunction "1_1") (pintype "passive"))
      (node (ref "JP9") (pin "1") (pinfunction "1_1") (pintype "passive"))
      (node (ref "JP9") (pin "2") (pinfunction "2_2") (pintype "passive"))
      (node (ref "JP9") (pin "3") (pinfunction "3_3") (pintype "passive"))
      (node (ref "JP9") (pin "4") (pinfunction "4_4") (pintype "passive"))
      (node (ref "JP9") (pin "5") (pinfunction "5_5") (pintype "passive"))
      (node (ref "JP9") (pin "6") (pinfunction "6_6") (pintype "passive"))
    )
    (net (code "36") (name "VCC") (class "Default")
      (node (ref "DC") (pin "1") (pinfunction "VIN_1") (pintype "passive"))
      (node (ref "J1") (pin "1") (pinfunction "1_1") (pintype "passive"))
      (node (ref "U2") (pin "1") (pinfunction "IN_1") (pintype "input"))
      (node (ref "U2") (pin "3") (pinfunction "EN_3") (pintype "input"))
      (node (ref "X1") (pin "VBUS") (pinfunction "VBUS_VBUS") (pintype "power_in"))
    )
    (net (code "37") (name "VDD") (class "Default")
      (node (ref "DC") (pin "3") (pinfunction "VOUT_3") (pintype "passive"))
      (node (ref "PAD10") (pin "1") (pinfunction "P_1") (pintype "passive"))
      (node (ref "PAD11") (pin "1") (pinfunction "P_1") (pintype "passive"))
      (node (ref "PAD12") (pin "1") (pinfunction "P_1") (pintype "passive"))
      (node (ref "PAD13") (pin "1") (pinfunction "P_1") (pintype "passive"))
      (node (ref "PAD14") (pin "1") (pinfunction "P_1") (pintype "passive"))
      (node (ref "PAD15") (pin "1") (pinfunction "P_1") (pintype "passive"))
      (node (ref "PAD16") (pin "1") (pinfunction "P_1") (pintype "passive"))
      (node (ref "PAD18") (pin "1") (pinfunction "P_1") (pintype "passive"))
      (node (ref "PAD19") (pin "1") (pinfunction "P_1") (pintype "passive"))
      (node (ref "PAD20") (pin "1") (pinfunction "P_1") (pintype "passive"))
      (node (ref "PAD21") (pin "1") (pinfunction "P_1") (pintype "passive"))
      (node (ref "PAD442") (pin "1") (pinfunction "P_1") (pintype "passive"))
      (node (ref "PAD443") (pin "1") (pinfunction "P_1") (pintype "passive"))
      (node (ref "PAD444") (pin "1") (pinfunction "P_1") (pintype "passive"))
      (node (ref "PAD445") (pin "1") (pinfunction "P_1") (pintype "passive"))
      (node (ref "PAD446") (pin "1") (pinfunction "P_1") (pintype "passive"))
      (node (ref "PAD447") (pin "1") (pinfunction "P_1") (pintype "passive"))
      (node (ref "PAD448") (pin "1") (pinfunction "P_1") (pintype "passive"))
      (node (ref "PAD449") (pin "1") (pinfunction "P_1") (pintype "passive"))
      (node (ref "PAD450") (pin "1") (pinfunction "P_1") (pintype "passive"))
      (node (ref "PAD451") (pin "1") (pinfunction "P_1") (pintype "passive"))
      (node (ref "PAD452") (pin "1") (pinfunction "P_1") (pintype "passive"))
      (node (ref "PAD453") (pin "1") (pinfunction "P_1") (pintype "passive"))
      (node (ref "PAD454") (pin "1") (pinfunction "P_1") (pintype "passive"))
      (node (ref "PAD455") (pin "1") (pinfunction "P_1") (pintype "passive"))
      (node (ref "PAD456") (pin "1") (pinfunction "P_1") (pintype "passive"))
      (node (ref "PAD459") (pin "1") (pinfunction "P_1") (pintype "passive"))
      (node (ref "PAD460") (pin "1") (pinfunction "P_1") (pintype "passive"))
      (node (ref "PAD461") (pin "1") (pinfunction "P_1") (pintype "passive"))
      (node (ref "PAD462") (pin "1") (pinfunction "P_1") (pintype "passive"))
      (node (ref "PAD5") (pin "1") (pinfunction "P_1") (pintype "passive"))
      (node (ref "PAD6") (pin "1") (pinfunction "P_1") (pintype "passive"))
      (node (ref "PAD7") (pin "1") (pinfunction "P_1") (pintype "passive"))
      (node (ref "PAD8") (pin "1") (pinfunction "P_1") (pintype "passive"))
      (node (ref "PAD9") (pin "1") (pinfunction "P_1") (pintype "passive"))
      (node (ref "U2") (pin "5") (pinfunction "OUT_5") (pintype "passive"))
    )
    (net (code "38") (name "unconnected-(U2-BP-Pad4)") (class "Default")
      (node (ref "U2") (pin "4") (pinfunction "BP_4") (pintype "input"))
    )
    (net (code "39") (name "unconnected-(X1-PadD+)") (class "Default")
      (node (ref "X1") (pin "D+") (pinfunction "D+_D+") (pintype "bidirectional"))
    )
    (net (code "40") (name "unconnected-(X1-PadD-)") (class "Default")
      (node (ref "X1") (pin "D-") (pinfunction "D-_D-") (pintype "bidirectional"))
    )
    (net (code "41") (name "unconnected-(X1-PadID)") (class "Default")
      (node (ref "X1") (pin "ID") (pinfunction "ID_ID") (pintype "bidirectional"))
    )
  )
)
